# mapleSDuino-V0_9_014-eagle7-test.net
KiCad netlist of a schematic drawn in EAGLE
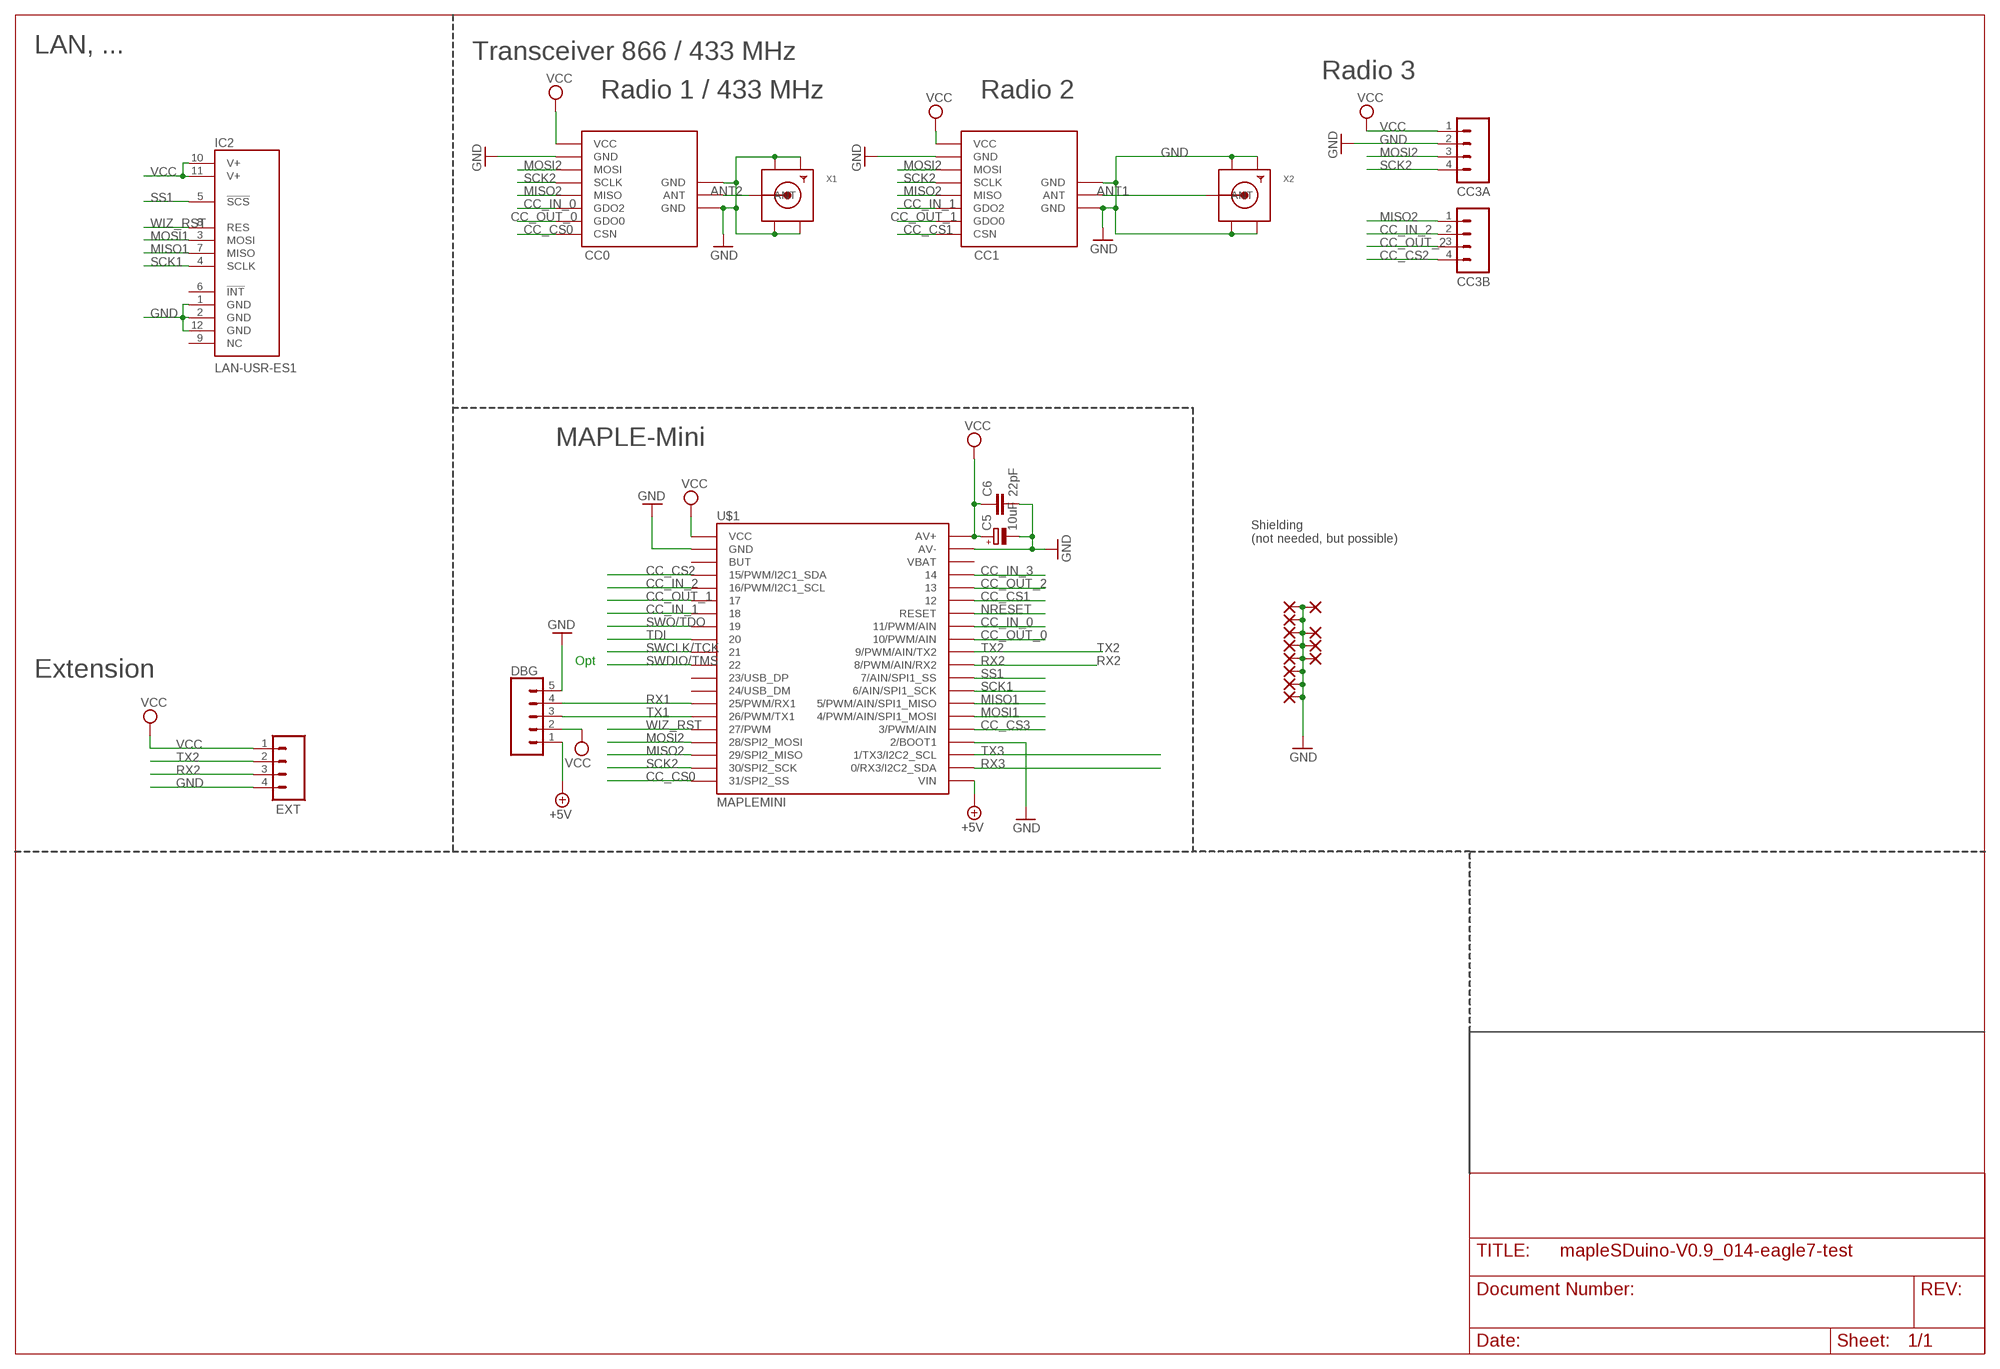
[diagram p0: schematic, sheet 1]

(export (version "E")
  (design (tool "Eeschema 10.0.6"))
  (components
    (comp (ref "C5")
      (value "10uF")
      (footprint "eagle-import:R_2012-12W")
      (libsource (lib "eagle-import") (part "CPOL-EUR/2012-12W"))
    )
    (comp (ref "C6")
      (value "22pF")
      (footprint "eagle-import:C0805")
      (libsource (lib "eagle-import") (part "C-EUC0805"))
    )
    (comp (ref "CC0")
      (value "CC1101")
      (footprint "eagle-import:CC1101_MODULE1_SMD")
      (libsource (lib "eagle-import") (part "CC1101_MODULE1SMD"))
    )
    (comp (ref "CC1")
      (value "CC1101_MODULE1SMD")
      (footprint "eagle-import:CC1101_MODULE1_SMD")
      (libsource (lib "eagle-import") (part "CC1101_MODULE1SMD"))
    )
    (comp (ref "CC3A")
      (value "CONN_04PTH")
      (footprint "eagle-import:1X04")
      (libsource (lib "eagle-import") (part "CONN_04PTH"))
    )
    (comp (ref "CC3B")
      (value "CONN_04PTH")
      (footprint "eagle-import:1X04")
      (libsource (lib "eagle-import") (part "CONN_04PTH"))
    )
    (comp (ref "DBG")
      (value "CONN_05LOCK")
      (footprint "eagle-import:1X05_LOCK")
      (libsource (lib "eagle-import") (part "CONN_05LOCK"))
    )
    (comp (ref "EXT")
      (value "CONN_04PTH")
      (footprint "eagle-import:1X04")
      (libsource (lib "eagle-import") (part "CONN_04PTH"))
    )
    (comp (ref "IC2")
      (value "LAN-USR-ES1")
      (footprint "eagle-import:USR-ES1")
      (libsource (lib "eagle-import") (part "LAN-USR-ES1"))
    )
    (comp (ref "PAD1")
      (value "WIREPADSMD1,27-254")
      (footprint "eagle-import:SMD1,27-2,54")
      (libsource (lib "eagle-import") (part "WIREPADSMD1,27-254"))
    )
    (comp (ref "PAD2")
      (value "WIREPADSMD1,27-254")
      (footprint "eagle-import:SMD1,27-2,54")
      (libsource (lib "eagle-import") (part "WIREPADSMD1,27-254"))
    )
    (comp (ref "PAD3")
      (value "WIREPADSMD1,27-254")
      (footprint "eagle-import:SMD1,27-2,54")
      (libsource (lib "eagle-import") (part "WIREPADSMD1,27-254"))
    )
    (comp (ref "PAD4")
      (value "WIREPADSMD1,27-254")
      (footprint "eagle-import:SMD1,27-2,54")
      (libsource (lib "eagle-import") (part "WIREPADSMD1,27-254"))
    )
    (comp (ref "PAD5")
      (value "WIREPADSMD1,27-254")
      (footprint "eagle-import:SMD1,27-2,54")
      (libsource (lib "eagle-import") (part "WIREPADSMD1,27-254"))
    )
    (comp (ref "PAD6")
      (value "WIREPADSMD1,27-254")
      (footprint "eagle-import:SMD1,27-2,54")
      (libsource (lib "eagle-import") (part "WIREPADSMD1,27-254"))
    )
    (comp (ref "PAD7")
      (value "WIREPADSMD1,27-254")
      (footprint "eagle-import:SMD1,27-2,54")
      (libsource (lib "eagle-import") (part "WIREPADSMD1,27-254"))
    )
    (comp (ref "PAD8")
      (value "WIREPADSMD1,27-254")
      (footprint "eagle-import:SMD1,27-2,54")
      (libsource (lib "eagle-import") (part "WIREPADSMD1,27-254"))
    )
    (comp (ref "PAD9")
      (value "WIREPADSMD1,27-254")
      (footprint "eagle-import:SMD1,27-2,54")
      (libsource (lib "eagle-import") (part "WIREPADSMD1,27-254"))
    )
    (comp (ref "PAD10")
      (value "WIREPADSMD1,27-254")
      (footprint "eagle-import:SMD1,27-2,54")
      (libsource (lib "eagle-import") (part "WIREPADSMD1,27-254"))
    )
    (comp (ref "PAD11")
      (value "WIREPADSMD1,27-254")
      (footprint "eagle-import:SMD1,27-2,54")
      (libsource (lib "eagle-import") (part "WIREPADSMD1,27-254"))
    )
    (comp (ref "PAD12")
      (value "WIREPADSMD1,27-254")
      (footprint "eagle-import:SMD1,27-2,54")
      (libsource (lib "eagle-import") (part "WIREPADSMD1,27-254"))
    )
    (comp (ref "U$1")
      (value "MAPLEMINI")
      (footprint "eagle-import:20-DIP")
      (libsource (lib "eagle-import") (part "MAPLEMINI"))
    )
    (comp (ref "X1")
      (value "SMACONNECTOR_EDGE")
      (footprint "eagle-import:SMA_EDGELAUNCH")
      (libsource (lib "eagle-import") (part "SMACONNECTOR_EDGE"))
    )
    (comp (ref "X2")
      (value "SMACONNECTOR_EDGE")
      (footprint "eagle-import:SMA_EDGELAUNCH")
      (libsource (lib "eagle-import") (part "SMACONNECTOR_EDGE"))
    )
  )
  (nets
    (net (code "1") (name "+5V") (class "Default")
      (node (ref "DBG") (pin "1") (pinfunction "1_1") (pintype "passive"))
      (node (ref "U$1") (pin "21") (pinfunction "VIN_21") (pintype "bidirectional"))
    )
    (net (code "2") (name "/ANT1") (class "Default")
      (node (ref "CC1") (pin "ANT") (pinfunction "ANT_ANT") (pintype "output"))
      (node (ref "X2") (pin "P") (pinfunction "ANT_P") (pintype "bidirectional"))
    )
    (net (code "3") (name "/ANT2") (class "Default")
      (node (ref "CC0") (pin "ANT") (pinfunction "ANT_ANT") (pintype "output"))
      (node (ref "X1") (pin "P") (pinfunction "ANT_P") (pintype "bidirectional"))
    )
    (net (code "4") (name "/CC_CS0") (class "Default")
      (node (ref "CC0") (pin "CSN") (pinfunction "CSN_CSN") (pintype "bidirectional"))
      (node (ref "U$1") (pin "20") (pinfunction "31/SPI2_SS_20") (pintype "bidirectional"))
    )
    (net (code "5") (name "/CC_CS1") (class "Default")
      (node (ref "CC1") (pin "CSN") (pinfunction "CSN_CSN") (pintype "bidirectional"))
      (node (ref "U$1") (pin "35") (pinfunction "12_35") (pintype "bidirectional"))
    )
    (net (code "6") (name "/CC_CS2") (class "Default")
      (node (ref "CC3B") (pin "4") (pinfunction "4_4") (pintype "passive"))
      (node (ref "U$1") (pin "4") (pinfunction "15/PWM/I2C1_SDA_4") (pintype "bidirectional"))
    )
    (net (code "7") (name "/CC_CS3") (class "Default")
      (node (ref "U$1") (pin "25") (pinfunction "3/PWM/AIN_25") (pintype "bidirectional"))
    )
    (net (code "8") (name "/CC_IN_0") (class "Default")
      (node (ref "CC0") (pin "GDO2") (pinfunction "GDO2_GDO2") (pintype "bidirectional"))
      (node (ref "U$1") (pin "33") (pinfunction "11/PWM/AIN_33") (pintype "bidirectional"))
    )
    (net (code "9") (name "/CC_IN_1") (class "Default")
      (node (ref "CC1") (pin "GDO2") (pinfunction "GDO2_GDO2") (pintype "bidirectional"))
      (node (ref "U$1") (pin "7") (pinfunction "18_7") (pintype "bidirectional"))
    )
    (net (code "10") (name "/CC_IN_2") (class "Default")
      (node (ref "CC3B") (pin "2") (pinfunction "2_2") (pintype "passive"))
      (node (ref "U$1") (pin "5") (pinfunction "16/PWM/I2C1_SCL_5") (pintype "bidirectional"))
    )
    (net (code "11") (name "/CC_IN_3") (class "Default")
      (node (ref "U$1") (pin "37") (pinfunction "14_37") (pintype "bidirectional"))
    )
    (net (code "12") (name "/CC_OUT_0") (class "Default")
      (node (ref "CC0") (pin "GDO0") (pinfunction "GDO0_GDO0") (pintype "bidirectional"))
      (node (ref "U$1") (pin "32") (pinfunction "10/PWM/AIN_32") (pintype "bidirectional"))
    )
    (net (code "13") (name "/CC_OUT_1") (class "Default")
      (node (ref "CC1") (pin "GDO0") (pinfunction "GDO0_GDO0") (pintype "bidirectional"))
      (node (ref "U$1") (pin "6") (pinfunction "17_6") (pintype "bidirectional"))
    )
    (net (code "14") (name "/CC_OUT_2") (class "Default")
      (node (ref "CC3B") (pin "3") (pinfunction "3_3") (pintype "passive"))
      (node (ref "U$1") (pin "36") (pinfunction "13_36") (pintype "bidirectional"))
    )
    (net (code "15") (name "/MISO1") (class "Default")
      (node (ref "IC2") (pin "7") (pinfunction "MISO_7") (pintype "bidirectional"))
      (node (ref "U$1") (pin "27") (pinfunction "5/PWM/AIN/SPI1_MISO_27") (pintype "bidirectional"))
    )
    (net (code "16") (name "/MISO2") (class "Default")
      (node (ref "CC0") (pin "MISO") (pinfunction "MISO_MISO") (pintype "bidirectional"))
      (node (ref "CC1") (pin "MISO") (pinfunction "MISO_MISO") (pintype "bidirectional"))
      (node (ref "CC3B") (pin "1") (pinfunction "1_1") (pintype "passive"))
      (node (ref "U$1") (pin "18") (pinfunction "29/SPI2_MISO_18") (pintype "bidirectional"))
    )
    (net (code "17") (name "/MOSI1") (class "Default")
      (node (ref "IC2") (pin "3") (pinfunction "MOSI_3") (pintype "bidirectional"))
      (node (ref "U$1") (pin "26") (pinfunction "4/PWM/AIN/SPI1_MOSI_26") (pintype "bidirectional"))
    )
    (net (code "18") (name "/MOSI2") (class "Default")
      (node (ref "CC0") (pin "MOSI") (pinfunction "MOSI_MOSI") (pintype "bidirectional"))
      (node (ref "CC1") (pin "MOSI") (pinfunction "MOSI_MOSI") (pintype "bidirectional"))
      (node (ref "CC3A") (pin "3") (pinfunction "3_3") (pintype "passive"))
      (node (ref "U$1") (pin "17") (pinfunction "28/SPI2_MOSI_17") (pintype "bidirectional"))
    )
    (net (code "19") (name "/NRESET") (class "Default")
      (node (ref "U$1") (pin "34") (pinfunction "RESET_34") (pintype "bidirectional"))
    )
    (net (code "20") (name "/RX1") (class "Default")
      (node (ref "DBG") (pin "4") (pinfunction "4_4") (pintype "passive"))
      (node (ref "U$1") (pin "14") (pinfunction "25/PWM/RX1_14") (pintype "bidirectional"))
    )
    (net (code "21") (name "/RX2") (class "Default")
      (node (ref "EXT") (pin "3") (pinfunction "3_3") (pintype "passive"))
      (node (ref "U$1") (pin "30") (pinfunction "8/PWM/AIN/RX2_30") (pintype "bidirectional"))
    )
    (net (code "22") (name "/RX3") (class "Default")
      (node (ref "U$1") (pin "22") (pinfunction "0/RX3/I2C2_SDA_22") (pintype "bidirectional"))
    )
    (net (code "23") (name "/SCK1") (class "Default")
      (node (ref "IC2") (pin "4") (pinfunction "SCLK_4") (pintype "input"))
      (node (ref "U$1") (pin "28") (pinfunction "6/AIN/SPI1_SCK_28") (pintype "bidirectional"))
    )
    (net (code "24") (name "/SCK2") (class "Default")
      (node (ref "CC0") (pin "SCLK") (pinfunction "SCLK_SCLK") (pintype "bidirectional"))
      (node (ref "CC1") (pin "SCLK") (pinfunction "SCLK_SCLK") (pintype "bidirectional"))
      (node (ref "CC3A") (pin "4") (pinfunction "4_4") (pintype "passive"))
      (node (ref "U$1") (pin "19") (pinfunction "30/SPI2_SCK_19") (pintype "bidirectional"))
    )
    (net (code "25") (name "/SS1") (class "Default")
      (node (ref "IC2") (pin "5") (pinfunction "~{SCS}_5") (pintype "input"))
      (node (ref "U$1") (pin "29") (pinfunction "7/AIN/SPI1_SS_29") (pintype "bidirectional"))
    )
    (net (code "26") (name "/SWCLK{slash}TCK") (class "Default")
      (node (ref "U$1") (pin "10") (pinfunction "21_10") (pintype "bidirectional"))
    )
    (net (code "27") (name "/SWDIO{slash}TMS") (class "Default")
      (node (ref "U$1") (pin "11") (pinfunction "22_11") (pintype "bidirectional"))
    )
    (net (code "28") (name "/SWO{slash}TDO") (class "Default")
      (node (ref "U$1") (pin "8") (pinfunction "19_8") (pintype "bidirectional"))
    )
    (net (code "29") (name "/TDI") (class "Default")
      (node (ref "U$1") (pin "9") (pinfunction "20_9") (pintype "bidirectional"))
    )
    (net (code "30") (name "/TX1") (class "Default")
      (node (ref "DBG") (pin "3") (pinfunction "3_3") (pintype "passive"))
      (node (ref "U$1") (pin "15") (pinfunction "26/PWM/TX1_15") (pintype "bidirectional"))
    )
    (net (code "31") (name "/TX2") (class "Default")
      (node (ref "EXT") (pin "2") (pinfunction "2_2") (pintype "passive"))
      (node (ref "U$1") (pin "31") (pinfunction "9/PWM/AIN/TX2_31") (pintype "bidirectional"))
    )
    (net (code "32") (name "/TX3") (class "Default")
      (node (ref "U$1") (pin "23") (pinfunction "1/TX3/I2C2_SCL_23") (pintype "bidirectional"))
    )
    (net (code "33") (name "/WIZ_RST") (class "Default")
      (node (ref "IC2") (pin "8") (pinfunction "RES_8") (pintype "input"))
      (node (ref "U$1") (pin "16") (pinfunction "27/PWM_16") (pintype "bidirectional"))
    )
    (net (code "34") (name "GND") (class "Default")
      (node (ref "C5") (pin "-") (pinfunction "-_-") (pintype "passive"))
      (node (ref "C6") (pin "2") (pinfunction "2_2") (pintype "passive"))
      (node (ref "CC0") (pin "GND@0") (pinfunction "GND_GND@0") (pintype "power_in"))
      (node (ref "CC0") (pin "GND@1") (pinfunction "GND_GND@1") (pintype "power_in"))
      (node (ref "CC0") (pin "GND@2") (pinfunction "GND_GND@2") (pintype "power_in"))
      (node (ref "CC1") (pin "GND@0") (pinfunction "GND_GND@0") (pintype "power_in"))
      (node (ref "CC1") (pin "GND@1") (pinfunction "GND_GND@1") (pintype "power_in"))
      (node (ref "CC1") (pin "GND@2") (pinfunction "GND_GND@2") (pintype "power_in"))
      (node (ref "CC3A") (pin "2") (pinfunction "2_2") (pintype "passive"))
      (node (ref "DBG") (pin "5") (pinfunction "5_5") (pintype "passive"))
      (node (ref "EXT") (pin "4") (pinfunction "4_4") (pintype "passive"))
      (node (ref "IC2") (pin "1") (pinfunction "GND_1") (pintype "power_in"))
      (node (ref "IC2") (pin "12") (pinfunction "GND_12") (pintype "power_in"))
      (node (ref "IC2") (pin "2") (pinfunction "GND_2") (pintype "power_in"))
      (node (ref "PAD1") (pin "1") (pinfunction "P_1") (pintype "passive"))
      (node (ref "PAD10") (pin "1") (pinfunction "P_1") (pintype "passive"))
      (node (ref "PAD11") (pin "1") (pinfunction "P_1") (pintype "passive"))
      (node (ref "PAD12") (pin "1") (pinfunction "P_1") (pintype "passive"))
      (node (ref "PAD2") (pin "1") (pinfunction "P_1") (pintype "passive"))
      (node (ref "PAD3") (pin "1") (pinfunction "P_1") (pintype "passive"))
      (node (ref "PAD4") (pin "1") (pinfunction "P_1") (pintype "passive"))
      (node (ref "PAD5") (pin "1") (pinfunction "P_1") (pintype "passive"))
      (node (ref "PAD6") (pin "1") (pinfunction "P_1") (pintype "passive"))
      (node (ref "PAD7") (pin "1") (pinfunction "P_1") (pintype "passive"))
      (node (ref "PAD8") (pin "1") (pinfunction "P_1") (pintype "passive"))
      (node (ref "PAD9") (pin "1") (pinfunction "P_1") (pintype "passive"))
      (node (ref "U$1") (pin "2") (pinfunction "GND_2") (pintype "bidirectional"))
      (node (ref "U$1") (pin "24") (pinfunction "2/BOOT1_24") (pintype "bidirectional"))
      (node (ref "U$1") (pin "39") (pinfunction "AV-_39") (pintype "bidirectional"))
      (node (ref "X1") (pin "GND@1") (pinfunction "GND4_GND@1") (pintype "power_in"))
      (node (ref "X1") (pin "GND@2") (pinfunction "GND3_GND@2") (pintype "power_in"))
      (node (ref "X1") (pin "GND@3") (pinfunction "GND2_GND@3") (pintype "power_in"))
      (node (ref "X1") (pin "GND@4") (pinfunction "GND1_GND@4") (pintype "power_in"))
      (node (ref "X2") (pin "GND@1") (pinfunction "GND4_GND@1") (pintype "power_in"))
      (node (ref "X2") (pin "GND@2") (pinfunction "GND3_GND@2") (pintype "power_in"))
      (node (ref "X2") (pin "GND@3") (pinfunction "GND2_GND@3") (pintype "power_in"))
      (node (ref "X2") (pin "GND@4") (pinfunction "GND1_GND@4") (pintype "power_in"))
    )
    (net (code "35") (name "VCC") (class "Default")
      (node (ref "C5") (pin "+") (pinfunction "+_+") (pintype "passive"))
      (node (ref "C6") (pin "1") (pinfunction "1_1") (pintype "passive"))
      (node (ref "CC0") (pin "VCC") (pinfunction "VCC_VCC") (pintype "power_in"))
      (node (ref "CC1") (pin "VCC") (pinfunction "VCC_VCC") (pintype "power_in"))
      (node (ref "CC3A") (pin "1") (pinfunction "1_1") (pintype "passive"))
      (node (ref "DBG") (pin "2") (pinfunction "2_2") (pintype "passive"))
      (node (ref "EXT") (pin "1") (pinfunction "1_1") (pintype "passive"))
      (node (ref "IC2") (pin "10") (pinfunction "V+_10") (pintype "power_in"))
      (node (ref "IC2") (pin "11") (pinfunction "V+_11") (pintype "power_in"))
      (node (ref "U$1") (pin "1") (pinfunction "VCC_1") (pintype "bidirectional"))
      (node (ref "U$1") (pin "40") (pinfunction "AV+_40") (pintype "bidirectional"))
    )
    (net (code "36") (name "unconnected-(IC2-NC-Pad9)") (class "Default")
      (node (ref "IC2") (pin "9") (pinfunction "NC_9") (pintype "no_connect"))
    )
    (net (code "37") (name "unconnected-(IC2-~{INT}-Pad6)") (class "Default")
      (node (ref "IC2") (pin "6") (pinfunction "~{INT}_6") (pintype "output"))
    )
    (net (code "38") (name "unconnected-(U$1-23{slash}USB_DP-Pad12)") (class "Default")
      (node (ref "U$1") (pin "12") (pinfunction "23/USB_DP_12") (pintype "bidirectional"))
    )
    (net (code "39") (name "unconnected-(U$1-24{slash}USB_DM-Pad13)") (class "Default")
      (node (ref "U$1") (pin "13") (pinfunction "24/USB_DM_13") (pintype "bidirectional"))
    )
    (net (code "40") (name "unconnected-(U$1-BUT-Pad3)") (class "Default")
      (node (ref "U$1") (pin "3") (pinfunction "BUT_3") (pintype "bidirectional"))
    )
    (net (code "41") (name "unconnected-(U$1-VBAT-Pad38)") (class "Default")
      (node (ref "U$1") (pin "38") (pinfunction "VBAT_38") (pintype "bidirectional"))
    )
  )
)
